# Digital_Audio_Amp.net
KiCad netlist of a schematic drawn in Altium Designer
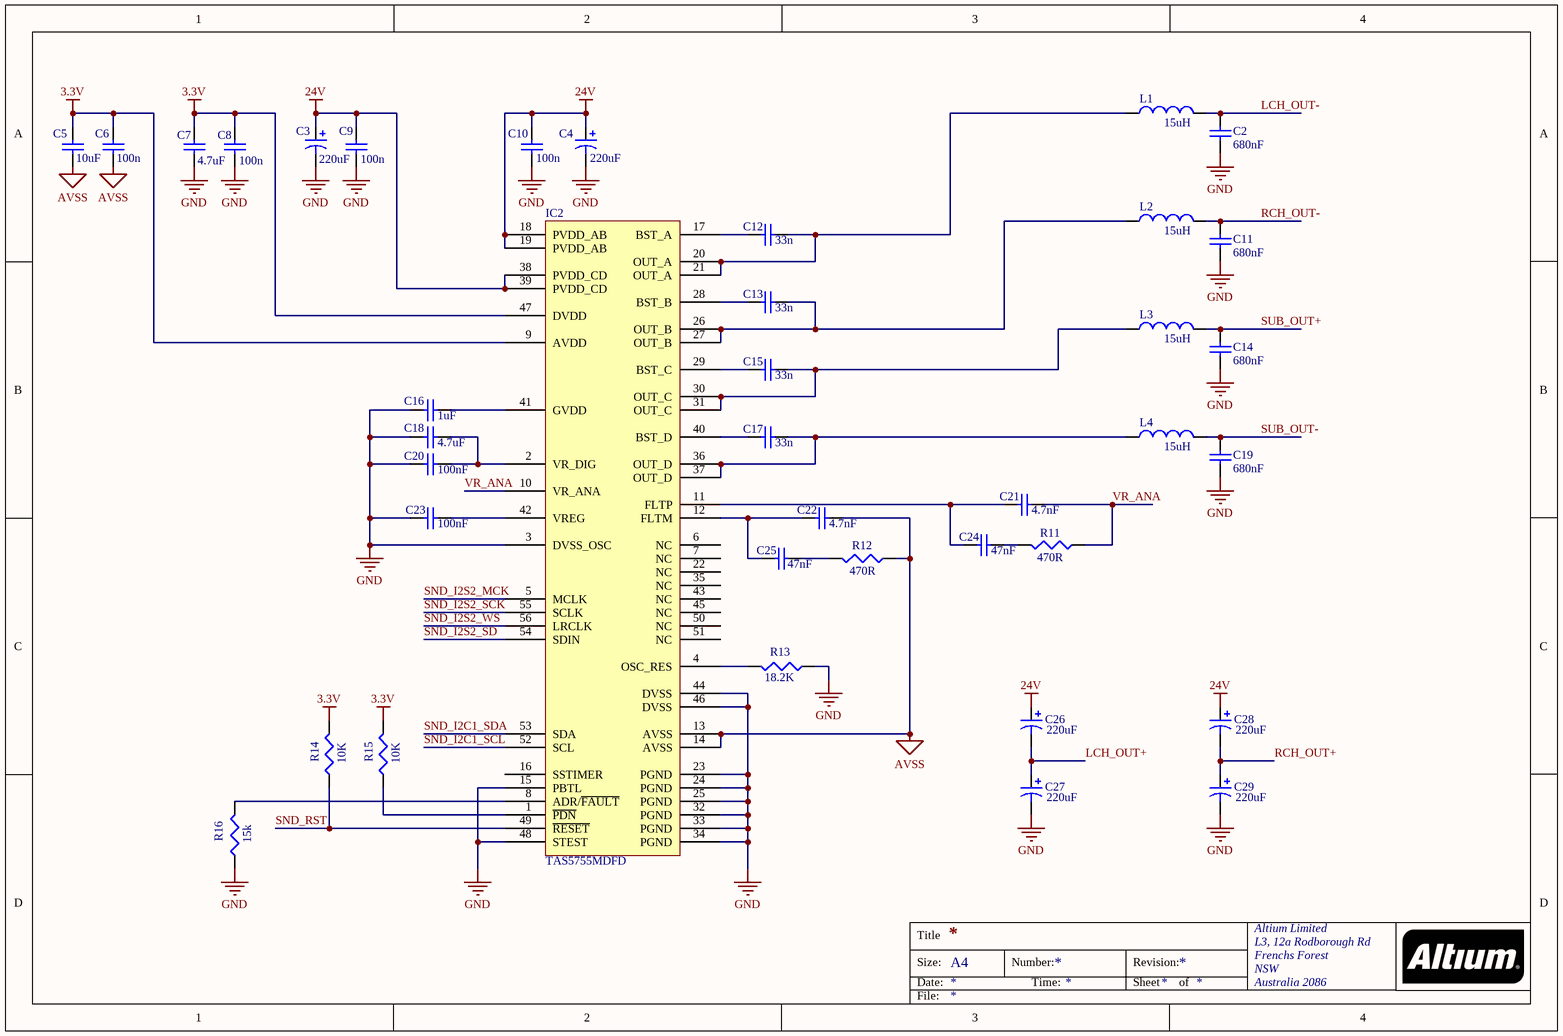
[diagram p0: Digital Audio Amp.SchDoc]

(export (version "E")
  (design (tool "Eeschema 10.0.6"))
  (components
    (comp (ref "C2")
      (value "680nF")
      (footprint "1206C-GENERIC")
      (description "Capacitor (Semiconductor SIM Model)")
      (fields (field (name "Comment") "Cap Semi") (field (name "PUBLISHER") "Altium Limited"))
      (libsource (lib "Miscellaneous Devices") (part "Cap Semi"))
    )
    (comp (ref "C3")
      (value "220uF")
      (footprint "PANACAP-F-GENERIC")
      (description "Polarized Capacitor (Surface Mount)")
      (fields (field (name "Comment") "Cap Pol3") (field (name "PUBLISHER") "Altium Limited"))
      (libsource (lib "Miscellaneous Devices") (part "Cap Pol3"))
    )
    (comp (ref "C4")
      (value "220uF")
      (footprint "PANACAP-F-GENERIC")
      (description "Polarized Capacitor (Surface Mount)")
      (fields (field (name "Comment") "Cap Pol3") (field (name "PUBLISHER") "Altium Limited"))
      (libsource (lib "Miscellaneous Devices") (part "Cap Pol3"))
    )
    (comp (ref "C5")
      (value "10uF")
      (footprint "0805C-GENERIC")
      (description "Capacitor (Semiconductor SIM Model)")
      (fields (field (name "Comment") "Cap Semi") (field (name "PUBLISHER") "Altium Limited"))
      (libsource (lib "Miscellaneous Devices") (part "Cap Semi"))
    )
    (comp (ref "C6")
      (value "100n")
      (footprint "0805C-GENERIC")
      (description "Capacitor (Semiconductor SIM Model)")
      (fields (field (name "Comment") "Cap Semi") (field (name "PUBLISHER") "Altium Limited"))
      (libsource (lib "Miscellaneous Devices") (part "Cap Semi"))
    )
    (comp (ref "C7")
      (value "4.7uF")
      (footprint "0805C-GENERIC")
      (description "Capacitor (Semiconductor SIM Model)")
      (fields (field (name "Comment") "Cap Semi") (field (name "PUBLISHER") "Altium Limited"))
      (libsource (lib "Miscellaneous Devices") (part "Cap Semi"))
    )
    (comp (ref "C8")
      (value "100n")
      (footprint "0805C-GENERIC")
      (description "Capacitor (Semiconductor SIM Model)")
      (fields (field (name "Comment") "Cap Semi") (field (name "PUBLISHER") "Altium Limited"))
      (libsource (lib "Miscellaneous Devices") (part "Cap Semi"))
    )
    (comp (ref "C9")
      (value "100n")
      (footprint "0805C-GENERIC")
      (description "Capacitor (Semiconductor SIM Model)")
      (fields (field (name "Comment") "Cap Semi") (field (name "PUBLISHER") "Altium Limited"))
      (libsource (lib "Miscellaneous Devices") (part "Cap Semi"))
    )
    (comp (ref "C10")
      (value "100n")
      (footprint "0805C-GENERIC")
      (description "Capacitor (Semiconductor SIM Model)")
      (fields (field (name "Comment") "Cap Semi") (field (name "PUBLISHER") "Altium Limited"))
      (libsource (lib "Miscellaneous Devices") (part "Cap Semi"))
    )
    (comp (ref "C11")
      (value "680nF")
      (footprint "1206C-GENERIC")
      (description "Capacitor (Semiconductor SIM Model)")
      (fields (field (name "Comment") "Cap Semi") (field (name "PUBLISHER") "Altium Limited"))
      (libsource (lib "Miscellaneous Devices") (part "Cap Semi"))
    )
    (comp (ref "C12")
      (value "33n")
      (footprint "1206C-GENERIC")
      (description "Capacitor (Semiconductor SIM Model)")
      (fields (field (name "Comment") "Cap Semi") (field (name "PUBLISHER") "Altium Limited"))
      (libsource (lib "Miscellaneous Devices") (part "Cap Semi"))
    )
    (comp (ref "C13")
      (value "33n")
      (footprint "1206C-GENERIC")
      (description "Capacitor (Semiconductor SIM Model)")
      (fields (field (name "Comment") "Cap Semi") (field (name "PUBLISHER") "Altium Limited"))
      (libsource (lib "Miscellaneous Devices") (part "Cap Semi"))
    )
    (comp (ref "C14")
      (value "680nF")
      (footprint "1206C-GENERIC")
      (description "Capacitor (Semiconductor SIM Model)")
      (fields (field (name "Comment") "Cap Semi") (field (name "PUBLISHER") "Altium Limited"))
      (libsource (lib "Miscellaneous Devices") (part "Cap Semi"))
    )
    (comp (ref "C15")
      (value "33n")
      (footprint "1206C-GENERIC")
      (description "Capacitor (Semiconductor SIM Model)")
      (fields (field (name "Comment") "Cap Semi") (field (name "PUBLISHER") "Altium Limited"))
      (libsource (lib "Miscellaneous Devices") (part "Cap Semi"))
    )
    (comp (ref "C16")
      (value "1uF")
      (footprint "0805C-GENERIC")
      (description "Capacitor (Semiconductor SIM Model)")
      (fields (field (name "Comment") "Cap Semi") (field (name "PUBLISHER") "Altium Limited"))
      (libsource (lib "Miscellaneous Devices") (part "Cap Semi"))
    )
    (comp (ref "C17")
      (value "33n")
      (footprint "1206C-GENERIC")
      (description "Capacitor (Semiconductor SIM Model)")
      (fields (field (name "Comment") "Cap Semi") (field (name "PUBLISHER") "Altium Limited"))
      (libsource (lib "Miscellaneous Devices") (part "Cap Semi"))
    )
    (comp (ref "C18")
      (value "4.7uF")
      (footprint "0805C-GENERIC")
      (description "Capacitor (Semiconductor SIM Model)")
      (fields (field (name "Comment") "Cap Semi") (field (name "PUBLISHER") "Altium Limited"))
      (libsource (lib "Miscellaneous Devices") (part "Cap Semi"))
    )
    (comp (ref "C19")
      (value "680nF")
      (footprint "1206C-GENERIC")
      (description "Capacitor (Semiconductor SIM Model)")
      (fields (field (name "Comment") "Cap Semi") (field (name "PUBLISHER") "Altium Limited"))
      (libsource (lib "Miscellaneous Devices") (part "Cap Semi"))
    )
    (comp (ref "C20")
      (value "100nF")
      (footprint "0805C-GENERIC")
      (description "Capacitor (Semiconductor SIM Model)")
      (fields (field (name "Comment") "Cap Semi") (field (name "PUBLISHER") "Altium Limited"))
      (libsource (lib "Miscellaneous Devices") (part "Cap Semi"))
    )
    (comp (ref "C21")
      (value "4.7nF")
      (footprint "0805C-GENERIC")
      (description "Capacitor (Semiconductor SIM Model)")
      (fields (field (name "Comment") "Cap Semi") (field (name "PUBLISHER") "Altium Limited"))
      (libsource (lib "Miscellaneous Devices") (part "Cap Semi"))
    )
    (comp (ref "C22")
      (value "4.7nF")
      (footprint "0805C-GENERIC")
      (description "Capacitor (Semiconductor SIM Model)")
      (fields (field (name "Comment") "Cap Semi") (field (name "PUBLISHER") "Altium Limited"))
      (libsource (lib "Miscellaneous Devices") (part "Cap Semi"))
    )
    (comp (ref "C23")
      (value "100nF")
      (footprint "0805C-GENERIC")
      (description "Capacitor (Semiconductor SIM Model)")
      (fields (field (name "Comment") "Cap Semi") (field (name "PUBLISHER") "Altium Limited"))
      (libsource (lib "Miscellaneous Devices") (part "Cap Semi"))
    )
    (comp (ref "C24")
      (value "47nF")
      (footprint "0805C-GENERIC")
      (description "Capacitor (Semiconductor SIM Model)")
      (fields (field (name "Comment") "Cap Semi") (field (name "PUBLISHER") "Altium Limited"))
      (libsource (lib "Miscellaneous Devices") (part "Cap Semi"))
    )
    (comp (ref "C25")
      (value "47nF")
      (footprint "0805C-GENERIC")
      (description "Capacitor (Semiconductor SIM Model)")
      (fields (field (name "Comment") "Cap Semi") (field (name "PUBLISHER") "Altium Limited"))
      (libsource (lib "Miscellaneous Devices") (part "Cap Semi"))
    )
    (comp (ref "C26")
      (value "220uF")
      (footprint "PANACAP-F-GENERIC")
      (description "Polarized Capacitor (Surface Mount)")
      (fields (field (name "Comment") "Cap Pol3") (field (name "PUBLISHER") "Altium Limited"))
      (libsource (lib "Miscellaneous Devices") (part "Cap Pol3"))
    )
    (comp (ref "C27")
      (value "220uF")
      (footprint "PANACAP-F-GENERIC")
      (description "Polarized Capacitor (Surface Mount)")
      (fields (field (name "Comment") "Cap Pol3") (field (name "PUBLISHER") "Altium Limited"))
      (libsource (lib "Miscellaneous Devices") (part "Cap Pol3"))
    )
    (comp (ref "C28")
      (value "220uF")
      (footprint "PANACAP-F-GENERIC")
      (description "Polarized Capacitor (Surface Mount)")
      (fields (field (name "Comment") "Cap Pol3") (field (name "PUBLISHER") "Altium Limited"))
      (libsource (lib "Miscellaneous Devices") (part "Cap Pol3"))
    )
    (comp (ref "C29")
      (value "220uF")
      (footprint "PANACAP-F-GENERIC")
      (description "Polarized Capacitor (Surface Mount)")
      (fields (field (name "Comment") "Cap Pol3") (field (name "PUBLISHER") "Altium Limited"))
      (libsource (lib "Miscellaneous Devices") (part "Cap Pol3"))
    )
    (comp (ref "IC2")
      (value "TAS5755MDFD")
      (footprint "DFD (R-PDSO-G56)")
      (description "2x50W(2x19W + 1x50W) Digital Input Class-D Audio Amplifier with Processing and 2.1 Mode Support")
      (libsource (lib "Texas_Instruments") (part "TAS5755MDFD"))
    )
    (comp (ref "L1")
      (value "15uH")
      (footprint "7447709150")
      (description "Inductor")
      (fields (field (name "PUBLISHER") "Altium Limited"))
      (libsource (lib "Miscellaneous Devices") (part "Inductor"))
    )
    (comp (ref "L2")
      (value "15uH")
      (footprint "7447709150")
      (description "Inductor")
      (fields (field (name "PUBLISHER") "Altium Limited"))
      (libsource (lib "Miscellaneous Devices") (part "Inductor"))
    )
    (comp (ref "L3")
      (value "15uH")
      (footprint "7447709150")
      (description "Inductor")
      (fields (field (name "PUBLISHER") "Altium Limited"))
      (libsource (lib "Miscellaneous Devices") (part "Inductor"))
    )
    (comp (ref "L4")
      (value "15uH")
      (footprint "7447709150")
      (description "Inductor")
      (fields (field (name "PUBLISHER") "Altium Limited"))
      (libsource (lib "Miscellaneous Devices") (part "Inductor"))
    )
    (comp (ref "R11")
      (value "470R")
      (footprint "0805R-GENERIC")
      (description "Resistor")
      (fields (field (name "Comment") "Res3") (field (name "PUBLISHER") "Altium Limited"))
      (libsource (lib "Miscellaneous Devices") (part "Res3"))
    )
    (comp (ref "R12")
      (value "470R")
      (footprint "0805R-GENERIC")
      (description "Resistor")
      (fields (field (name "Comment") "Res3") (field (name "PUBLISHER") "Altium Limited"))
      (libsource (lib "Miscellaneous Devices") (part "Res3"))
    )
    (comp (ref "R13")
      (value "18.2K")
      (footprint "0805R-GENERIC")
      (description "Resistor")
      (fields (field (name "Comment") "Res3") (field (name "PUBLISHER") "Altium Limited"))
      (libsource (lib "Miscellaneous Devices") (part "Res3"))
    )
    (comp (ref "R14")
      (value "10K")
      (footprint "0805R-GENERIC")
      (description "Resistor")
      (fields (field (name "Comment") "Res3") (field (name "PUBLISHER") "Altium Limited"))
      (libsource (lib "Miscellaneous Devices") (part "Res3"))
    )
    (comp (ref "R15")
      (value "10K")
      (footprint "0805R-GENERIC")
      (description "Resistor")
      (fields (field (name "Comment") "Res3") (field (name "PUBLISHER") "Altium Limited"))
      (libsource (lib "Miscellaneous Devices") (part "Res3"))
    )
    (comp (ref "R16")
      (value "15k")
      (footprint "0805R-GENERIC")
      (description "Resistor")
      (fields (field (name "Comment") "Res3") (field (name "PUBLISHER") "Altium Limited"))
      (libsource (lib "Miscellaneous Devices") (part "Res3"))
    )
  )
  (nets
    (net (code "1") (name "/LCH_OUT+") (class "Default")
      (node (ref "C26") (pin "2") (pinfunction "2_2") (pintype "passive"))
      (node (ref "C27") (pin "1") (pinfunction "1_1") (pintype "passive"))
    )
    (net (code "2") (name "/LCH_OUT-") (class "Default")
      (node (ref "C2") (pin "1") (pinfunction "1_1") (pintype "passive"))
      (node (ref "L1") (pin "2") (pinfunction "2_2") (pintype "passive"))
    )
    (net (code "3") (name "/RCH_OUT+") (class "Default")
      (node (ref "C28") (pin "2") (pinfunction "2_2") (pintype "passive"))
      (node (ref "C29") (pin "1") (pinfunction "1_1") (pintype "passive"))
    )
    (net (code "4") (name "/RCH_OUT-") (class "Default")
      (node (ref "C11") (pin "1") (pinfunction "1_1") (pintype "passive"))
      (node (ref "L2") (pin "2") (pinfunction "2_2") (pintype "passive"))
    )
    (net (code "5") (name "/SND_I2C1_SCL") (class "Default")
      (node (ref "IC2") (pin "52") (pinfunction "SCL_52") (pintype "passive"))
    )
    (net (code "6") (name "/SND_I2C1_SDA") (class "Default")
      (node (ref "IC2") (pin "53") (pinfunction "SDA_53") (pintype "passive"))
    )
    (net (code "7") (name "/SND_I2S2_MCK") (class "Default")
      (node (ref "IC2") (pin "5") (pinfunction "MCLK_5") (pintype "passive"))
    )
    (net (code "8") (name "/SND_I2S2_SCK") (class "Default")
      (node (ref "IC2") (pin "55") (pinfunction "SCLK_55") (pintype "passive"))
    )
    (net (code "9") (name "/SND_I2S2_SD") (class "Default")
      (node (ref "IC2") (pin "54") (pinfunction "SDIN_54") (pintype "passive"))
    )
    (net (code "10") (name "/SND_I2S2_WS") (class "Default")
      (node (ref "IC2") (pin "56") (pinfunction "LRCLK_56") (pintype "passive"))
    )
    (net (code "11") (name "/SND_RST") (class "Default")
      (node (ref "IC2") (pin "49") (pinfunction "~{RESET}_49") (pintype "passive"))
      (node (ref "R14") (pin "1") (pinfunction "1_1") (pintype "passive"))
    )
    (net (code "12") (name "/SUB_OUT+") (class "Default")
      (node (ref "C14") (pin "1") (pinfunction "1_1") (pintype "passive"))
      (node (ref "L3") (pin "2") (pinfunction "2_2") (pintype "passive"))
    )
    (net (code "13") (name "/SUB_OUT-") (class "Default")
      (node (ref "C19") (pin "1") (pinfunction "1_1") (pintype "passive"))
      (node (ref "L4") (pin "2") (pinfunction "2_2") (pintype "passive"))
    )
    (net (code "14") (name "/VR_ANA") (class "Default")
      (node (ref "C21") (pin "1") (pinfunction "1_1") (pintype "passive"))
      (node (ref "IC2") (pin "10") (pinfunction "VR_ANA_10") (pintype "passive"))
      (node (ref "R11") (pin "1") (pinfunction "1_1") (pintype "passive"))
    )
    (net (code "15") (name "3.3V") (class "Default")
      (node (ref "C5") (pin "1") (pinfunction "1_1") (pintype "passive"))
      (node (ref "C6") (pin "2") (pinfunction "2_2") (pintype "passive"))
      (node (ref "C7") (pin "2") (pinfunction "2_2") (pintype "passive"))
      (node (ref "C8") (pin "2") (pinfunction "2_2") (pintype "passive"))
      (node (ref "IC2") (pin "47") (pinfunction "DVDD_47") (pintype "passive"))
      (node (ref "IC2") (pin "9") (pinfunction "AVDD_9") (pintype "passive"))
      (node (ref "R14") (pin "2") (pinfunction "2_2") (pintype "passive"))
      (node (ref "R15") (pin "2") (pinfunction "2_2") (pintype "passive"))
    )
    (net (code "16") (name "24V") (class "Default")
      (node (ref "C10") (pin "2") (pinfunction "2_2") (pintype "passive"))
      (node (ref "C26") (pin "1") (pinfunction "1_1") (pintype "passive"))
      (node (ref "C28") (pin "1") (pinfunction "1_1") (pintype "passive"))
      (node (ref "C3") (pin "1") (pinfunction "1_1") (pintype "passive"))
      (node (ref "C4") (pin "1") (pinfunction "1_1") (pintype "passive"))
      (node (ref "C9") (pin "2") (pinfunction "2_2") (pintype "passive"))
      (node (ref "IC2") (pin "18") (pinfunction "PVDD_AB_18") (pintype "passive"))
      (node (ref "IC2") (pin "19") (pinfunction "PVDD_AB_19") (pintype "passive"))
      (node (ref "IC2") (pin "38") (pinfunction "PVDD_CD_38") (pintype "passive"))
      (node (ref "IC2") (pin "39") (pinfunction "PVDD_CD_39") (pintype "passive"))
    )
    (net (code "17") (name "AVSS") (class "Default")
      (node (ref "C22") (pin "1") (pinfunction "1_1") (pintype "passive"))
      (node (ref "C5") (pin "2") (pinfunction "2_2") (pintype "passive"))
      (node (ref "C6") (pin "1") (pinfunction "1_1") (pintype "passive"))
      (node (ref "IC2") (pin "13") (pinfunction "AVSS_13") (pintype "passive"))
      (node (ref "IC2") (pin "14") (pinfunction "AVSS_14") (pintype "passive"))
      (node (ref "R12") (pin "1") (pinfunction "1_1") (pintype "passive"))
    )
    (net (code "18") (name "GND") (class "Default")
      (node (ref "C10") (pin "1") (pinfunction "1_1") (pintype "passive"))
      (node (ref "C11") (pin "2") (pinfunction "2_2") (pintype "passive"))
      (node (ref "C14") (pin "2") (pinfunction "2_2") (pintype "passive"))
      (node (ref "C16") (pin "2") (pinfunction "2_2") (pintype "passive"))
      (node (ref "C18") (pin "2") (pinfunction "2_2") (pintype "passive"))
      (node (ref "C19") (pin "2") (pinfunction "2_2") (pintype "passive"))
      (node (ref "C2") (pin "2") (pinfunction "2_2") (pintype "passive"))
      (node (ref "C20") (pin "2") (pinfunction "2_2") (pintype "passive"))
      (node (ref "C23") (pin "2") (pinfunction "2_2") (pintype "passive"))
      (node (ref "C27") (pin "2") (pinfunction "2_2") (pintype "passive"))
      (node (ref "C29") (pin "2") (pinfunction "2_2") (pintype "passive"))
      (node (ref "C3") (pin "2") (pinfunction "2_2") (pintype "passive"))
      (node (ref "C4") (pin "2") (pinfunction "2_2") (pintype "passive"))
      (node (ref "C7") (pin "1") (pinfunction "1_1") (pintype "passive"))
      (node (ref "C8") (pin "1") (pinfunction "1_1") (pintype "passive"))
      (node (ref "C9") (pin "1") (pinfunction "1_1") (pintype "passive"))
      (node (ref "IC2") (pin "15") (pinfunction "PBTL_15") (pintype "passive"))
      (node (ref "IC2") (pin "23") (pinfunction "PGND_23") (pintype "passive"))
      (node (ref "IC2") (pin "24") (pinfunction "PGND_24") (pintype "passive"))
      (node (ref "IC2") (pin "25") (pinfunction "PGND_25") (pintype "passive"))
      (node (ref "IC2") (pin "3") (pinfunction "DVSS_OSC_3") (pintype "passive"))
      (node (ref "IC2") (pin "32") (pinfunction "PGND_32") (pintype "passive"))
      (node (ref "IC2") (pin "33") (pinfunction "PGND_33") (pintype "passive"))
      (node (ref "IC2") (pin "34") (pinfunction "PGND_34") (pintype "passive"))
      (node (ref "IC2") (pin "44") (pinfunction "DVSS_44") (pintype "passive"))
      (node (ref "IC2") (pin "46") (pinfunction "DVSS_46") (pintype "passive"))
      (node (ref "IC2") (pin "48") (pinfunction "STEST_48") (pintype "passive"))
      (node (ref "R13") (pin "1") (pinfunction "1_1") (pintype "passive"))
      (node (ref "R16") (pin "1") (pinfunction "1_1") (pintype "passive"))
    )
    (net (code "19") (name "Net-(C12-Pad1)") (class "Default")
      (node (ref "C12") (pin "1") (pinfunction "1_1") (pintype "passive"))
      (node (ref "IC2") (pin "20") (pinfunction "OUT_A_20") (pintype "passive"))
      (node (ref "IC2") (pin "21") (pinfunction "OUT_A_21") (pintype "passive"))
      (node (ref "L1") (pin "1") (pinfunction "1_1") (pintype "passive"))
    )
    (net (code "20") (name "Net-(C13-Pad1)") (class "Default")
      (node (ref "C13") (pin "1") (pinfunction "1_1") (pintype "passive"))
      (node (ref "IC2") (pin "26") (pinfunction "OUT_B_26") (pintype "passive"))
      (node (ref "IC2") (pin "27") (pinfunction "OUT_B_27") (pintype "passive"))
      (node (ref "L2") (pin "1") (pinfunction "1_1") (pintype "passive"))
    )
    (net (code "21") (name "Net-(C15-Pad1)") (class "Default")
      (node (ref "C15") (pin "1") (pinfunction "1_1") (pintype "passive"))
      (node (ref "IC2") (pin "30") (pinfunction "OUT_C_30") (pintype "passive"))
      (node (ref "IC2") (pin "31") (pinfunction "OUT_C_31") (pintype "passive"))
      (node (ref "L3") (pin "1") (pinfunction "1_1") (pintype "passive"))
    )
    (net (code "22") (name "Net-(C17-Pad1)") (class "Default")
      (node (ref "C17") (pin "1") (pinfunction "1_1") (pintype "passive"))
      (node (ref "IC2") (pin "36") (pinfunction "OUT_D_36") (pintype "passive"))
      (node (ref "IC2") (pin "37") (pinfunction "OUT_D_37") (pintype "passive"))
      (node (ref "L4") (pin "1") (pinfunction "1_1") (pintype "passive"))
    )
    (net (code "23") (name "Net-(C24-Pad1)") (class "Default")
      (node (ref "C24") (pin "1") (pinfunction "1_1") (pintype "passive"))
      (node (ref "R11") (pin "2") (pinfunction "2_2") (pintype "passive"))
    )
    (net (code "24") (name "Net-(C25-Pad1)") (class "Default")
      (node (ref "C25") (pin "1") (pinfunction "1_1") (pintype "passive"))
      (node (ref "R12") (pin "2") (pinfunction "2_2") (pintype "passive"))
    )
    (net (code "25") (name "Net-(IC2-ADR{slash}~{FAULT})") (class "Default")
      (node (ref "IC2") (pin "8") (pinfunction "ADR/~{FAULT}_8") (pintype "passive"))
      (node (ref "R16") (pin "2") (pinfunction "2_2") (pintype "passive"))
    )
    (net (code "26") (name "Net-(IC2-BST_A)") (class "Default")
      (node (ref "C12") (pin "2") (pinfunction "2_2") (pintype "passive"))
      (node (ref "IC2") (pin "17") (pinfunction "BST_A_17") (pintype "passive"))
    )
    (net (code "27") (name "Net-(IC2-BST_B)") (class "Default")
      (node (ref "C13") (pin "2") (pinfunction "2_2") (pintype "passive"))
      (node (ref "IC2") (pin "28") (pinfunction "BST_B_28") (pintype "passive"))
    )
    (net (code "28") (name "Net-(IC2-BST_C)") (class "Default")
      (node (ref "C15") (pin "2") (pinfunction "2_2") (pintype "passive"))
      (node (ref "IC2") (pin "29") (pinfunction "BST_C_29") (pintype "passive"))
    )
    (net (code "29") (name "Net-(IC2-BST_D)") (class "Default")
      (node (ref "C17") (pin "2") (pinfunction "2_2") (pintype "passive"))
      (node (ref "IC2") (pin "40") (pinfunction "BST_D_40") (pintype "passive"))
    )
    (net (code "30") (name "Net-(IC2-FLTM)") (class "Default")
      (node (ref "C22") (pin "2") (pinfunction "2_2") (pintype "passive"))
      (node (ref "C25") (pin "2") (pinfunction "2_2") (pintype "passive"))
      (node (ref "IC2") (pin "12") (pinfunction "FLTM_12") (pintype "passive"))
    )
    (net (code "31") (name "Net-(IC2-FLTP)") (class "Default")
      (node (ref "C21") (pin "2") (pinfunction "2_2") (pintype "passive"))
      (node (ref "C24") (pin "2") (pinfunction "2_2") (pintype "passive"))
      (node (ref "IC2") (pin "11") (pinfunction "FLTP_11") (pintype "passive"))
    )
    (net (code "32") (name "Net-(IC2-GVDD)") (class "Default")
      (node (ref "C16") (pin "1") (pinfunction "1_1") (pintype "passive"))
      (node (ref "IC2") (pin "41") (pinfunction "GVDD_41") (pintype "passive"))
    )
    (net (code "33") (name "Net-(IC2-OSC_RES)") (class "Default")
      (node (ref "IC2") (pin "4") (pinfunction "OSC_RES_4") (pintype "passive"))
      (node (ref "R13") (pin "2") (pinfunction "2_2") (pintype "passive"))
    )
    (net (code "34") (name "Net-(IC2-VREG)") (class "Default")
      (node (ref "C23") (pin "1") (pinfunction "1_1") (pintype "passive"))
      (node (ref "IC2") (pin "42") (pinfunction "VREG_42") (pintype "passive"))
    )
    (net (code "35") (name "Net-(IC2-VR_DIG)") (class "Default")
      (node (ref "C18") (pin "1") (pinfunction "1_1") (pintype "passive"))
      (node (ref "C20") (pin "1") (pinfunction "1_1") (pintype "passive"))
      (node (ref "IC2") (pin "2") (pinfunction "VR_DIG_2") (pintype "passive"))
    )
    (net (code "36") (name "Net-(IC2-~{PDN})") (class "Default")
      (node (ref "IC2") (pin "1") (pinfunction "~{PDN}_1") (pintype "passive"))
      (node (ref "R15") (pin "1") (pinfunction "1_1") (pintype "passive"))
    )
    (net (code "37") (name "unconnected-(IC2-NC-Pad6)") (class "Default")
      (node (ref "IC2") (pin "6") (pinfunction "NC_6") (pintype "passive"))
    )
    (net (code "38") (name "unconnected-(IC2-NC-Pad7)") (class "Default")
      (node (ref "IC2") (pin "7") (pinfunction "NC_7") (pintype "passive"))
    )
    (net (code "39") (name "unconnected-(IC2-NC-Pad22)") (class "Default")
      (node (ref "IC2") (pin "22") (pinfunction "NC_22") (pintype "passive"))
    )
    (net (code "40") (name "unconnected-(IC2-NC-Pad35)") (class "Default")
      (node (ref "IC2") (pin "35") (pinfunction "NC_35") (pintype "passive"))
    )
    (net (code "41") (name "unconnected-(IC2-NC-Pad43)") (class "Default")
      (node (ref "IC2") (pin "43") (pinfunction "NC_43") (pintype "passive"))
    )
    (net (code "42") (name "unconnected-(IC2-NC-Pad45)") (class "Default")
      (node (ref "IC2") (pin "45") (pinfunction "NC_45") (pintype "passive"))
    )
    (net (code "43") (name "unconnected-(IC2-NC-Pad50)") (class "Default")
      (node (ref "IC2") (pin "50") (pinfunction "NC_50") (pintype "passive"))
    )
    (net (code "44") (name "unconnected-(IC2-NC-Pad51)") (class "Default")
      (node (ref "IC2") (pin "51") (pinfunction "NC_51") (pintype "passive"))
    )
    (net (code "45") (name "unconnected-(IC2-SSTIMER-Pad16)") (class "Default")
      (node (ref "IC2") (pin "16") (pinfunction "SSTIMER_16") (pintype "passive"))
    )
  )
)
